# 19_RADIATOR.net
KiCad netlist of a schematic drawn in Altium Designer
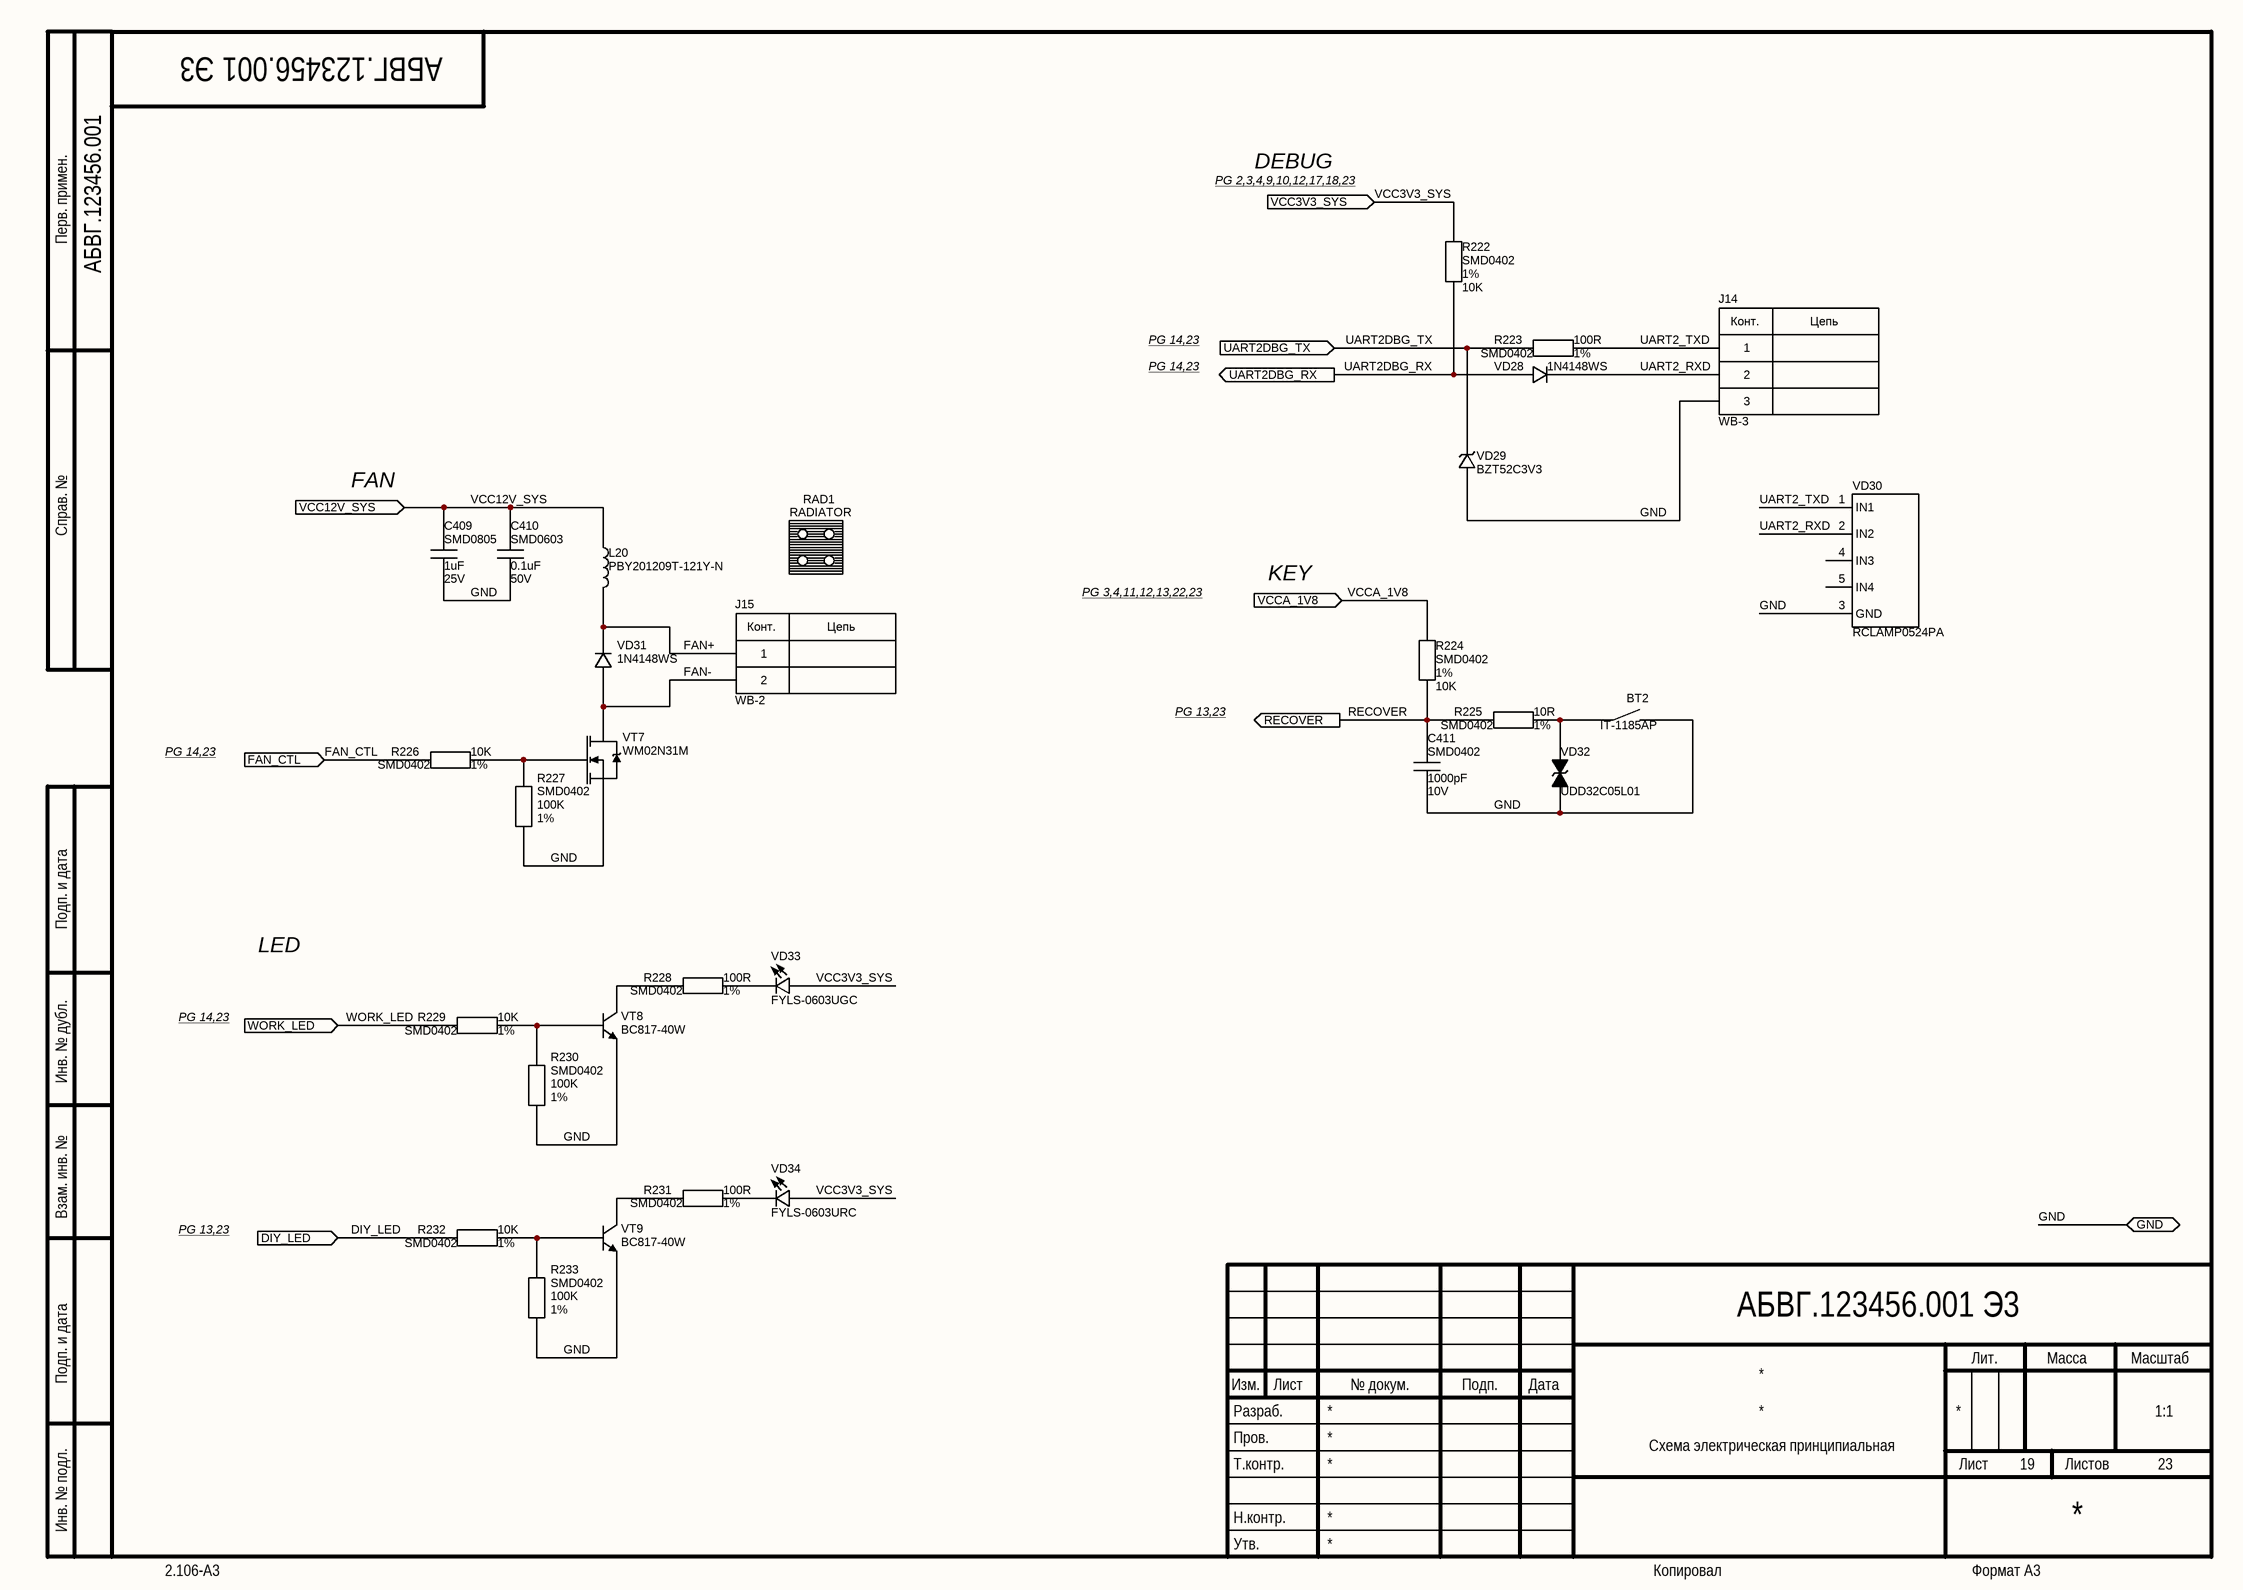
[diagram p0: 19 RADIATOR.SchDoc]

(export (version "E")
  (design (tool "Eeschema 10.0.6"))
  (components
    (comp (ref "BT2")
      (value "IT-1185AP")
      (footprint "Didur_PcbLib_1:IT-1185AP")
      (libsource (lib "Didur_SchLib_1") (part "Button_2pin"))
    )
    (comp (ref "C409")
      (value "1uF")
      (footprint "CAP_SMD_0805")
      (fields
        (field (name "PACKAGE") "SMD0805")
        (field (name "PARTNUMBER") "CC0805KKX7R8BB105")
        (field (name "VOLTAGE") "25V")
      )
      (libsource (lib "Didur_SchLib_1") (part "Ceramic_Cap"))
    )
    (comp (ref "C410")
      (value "0.1uF")
      (footprint "CAP_SMD_0603")
      (fields
        (field (name "PACKAGE") "SMD0603")
        (field (name "PARTNUMBER") "CC0603KRX7R9BB104")
        (field (name "VOLTAGE") "50V")
      )
      (libsource (lib "Didur_SchLib_1") (part "Ceramic_Cap"))
    )
    (comp (ref "C411")
      (value "1000pF")
      (footprint "Didur_PcbLib_1:CAP_SMD_0402")
      (fields
        (field (name "PACKAGE") "SMD0402")
        (field (name "PARTNUMBER") "CC0402KRX7R9BB102")
        (field (name "VOLTAGE") "10V")
      )
      (libsource (lib "Didur_SchLib_1") (part "Ceramic_Cap"))
    )
    (comp (ref "J14")
      (value "WB-3")
      (footprint "Didur_PcbLib_1:WB-3")
      (fields (field (name "PARTNUMBER") "DS1066-03M(MW-3M)"))
      (libsource (lib "Didur_SchLib_1") (part "CON3"))
    )
    (comp (ref "J15")
      (value "WB-2")
      (footprint "Didur_PcbLib_1:WB-2")
      (fields (field (name "PARTNUMBER") "DS1066-02M(MW-2M)"))
      (libsource (lib "Didur_SchLib_1") (part "CON2"))
    )
    (comp (ref "L20")
      (value "PBY201209T-121Y-N")
      (footprint "Didur_PcbLib_1:IND_SMD_0805")
      (fields (field (name "Comment") "Value"))
      (libsource (lib "Didur_SchLib_1") (part "Inductor_smal"))
    )
    (comp (ref "R222")
      (value "10K")
      (footprint "Didur_PcbLib_1:RES_SMD_0402")
      (fields
        (field (name "PACKAGE") "SMD0402")
        (field (name "PARTNUMBER") "RC0402FR-0710KL")
        (field (name "TOLERANCE") "1%")
      )
      (libsource (lib "Didur_SchLib_1") (part "Chip_Res"))
    )
    (comp (ref "R223")
      (value "100R")
      (footprint "Didur_PcbLib_1:RES_SMD_0402")
      (fields
        (field (name "PACKAGE") "SMD0402")
        (field (name "PARTNUMBER") "RC0402FR-07100RL")
        (field (name "TOLERANCE") "1%")
      )
      (libsource (lib "") (part "Chip_Res_2"))
    )
    (comp (ref "R224")
      (value "10K")
      (footprint "Didur_PcbLib_1:RES_SMD_0402")
      (fields
        (field (name "PACKAGE") "SMD0402")
        (field (name "PARTNUMBER") "RC0402FR-0710KL")
        (field (name "TOLERANCE") "1%")
      )
      (libsource (lib "Didur_SchLib_1") (part "Chip_Res"))
    )
    (comp (ref "R225")
      (value "10R")
      (footprint "Didur_PcbLib_1:RES_SMD_0402")
      (fields
        (field (name "PACKAGE") "SMD0402")
        (field (name "PARTNUMBER") "RC0402FR-0710RL")
        (field (name "TOLERANCE") "1%")
      )
      (libsource (lib "Didur_SchLib_1") (part "Chip_Res"))
    )
    (comp (ref "R226")
      (value "10K")
      (footprint "Didur_PcbLib_1:RES_SMD_0402")
      (fields
        (field (name "PACKAGE") "SMD0402")
        (field (name "PARTNUMBER") "RC0402FR-0710KL")
        (field (name "TOLERANCE") "1%")
      )
      (libsource (lib "") (part "Chip_Res_1"))
    )
    (comp (ref "R227")
      (value "100K")
      (footprint "Didur_PcbLib_1:RES_SMD_0402")
      (fields
        (field (name "PACKAGE") "SMD0402")
        (field (name "PARTNUMBER") "RC0402FR-07100KL")
        (field (name "TOLERANCE") "1%")
      )
      (libsource (lib "") (part "Chip_Res_2"))
    )
    (comp (ref "R228")
      (value "100R")
      (footprint "Didur_PcbLib_1:RES_SMD_0402")
      (fields
        (field (name "PACKAGE") "SMD0402")
        (field (name "PARTNUMBER") "RC0402FR-07100RL")
        (field (name "TOLERANCE") "1%")
      )
      (libsource (lib "") (part "Chip_Res_2"))
    )
    (comp (ref "R229")
      (value "10K")
      (footprint "Didur_PcbLib_1:RES_SMD_0402")
      (fields
        (field (name "PACKAGE") "SMD0402")
        (field (name "PARTNUMBER") "RC0402FR-0710KL")
        (field (name "TOLERANCE") "1%")
      )
      (libsource (lib "") (part "Chip_Res_1"))
    )
    (comp (ref "R230")
      (value "100K")
      (footprint "Didur_PcbLib_1:RES_SMD_0402")
      (fields
        (field (name "PACKAGE") "SMD0402")
        (field (name "PARTNUMBER") "RC0402FR-07100KL")
        (field (name "TOLERANCE") "1%")
      )
      (libsource (lib "") (part "Chip_Res_2"))
    )
    (comp (ref "R231")
      (value "100R")
      (footprint "Didur_PcbLib_1:RES_SMD_0402")
      (fields
        (field (name "PACKAGE") "SMD0402")
        (field (name "PARTNUMBER") "RC0402FR-07100RL")
        (field (name "TOLERANCE") "1%")
      )
      (libsource (lib "") (part "Chip_Res_2"))
    )
    (comp (ref "R232")
      (value "10K")
      (footprint "Didur_PcbLib_1:RES_SMD_0402")
      (fields
        (field (name "PACKAGE") "SMD0402")
        (field (name "PARTNUMBER") "RC0402FR-0710KL")
        (field (name "TOLERANCE") "1%")
      )
      (libsource (lib "") (part "Chip_Res_1"))
    )
    (comp (ref "R233")
      (value "100K")
      (footprint "Didur_PcbLib_1:RES_SMD_0402")
      (fields
        (field (name "PACKAGE") "SMD0402")
        (field (name "PARTNUMBER") "RC0402FR-07100KL")
        (field (name "TOLERANCE") "1%")
      )
      (libsource (lib "") (part "Chip_Res_2"))
    )
    (comp (ref "RAD1")
      (value "RADIATOR")
      (footprint "Didur_PcbLib_1:RK3399_RADIATOR_2")
      (libsource (lib "Didur_SchLib_1") (part "RK3399_RADIATOR_1"))
    )
    (comp (ref "VD28")
      (value "1N4148WS")
      (footprint "SOD323")
      (fields (field (name "Comment") "Diode"))
      (libsource (lib "Didur_SchLib_1") (part "Diode"))
    )
    (comp (ref "VD29")
      (value "BZT52C3V3")
      (footprint "Didur_PcbLib_1:SOD323")
      (libsource (lib "Didur_SchLib_1") (part "ZenerDiode"))
    )
    (comp (ref "VD30")
      (value "RCLAMP0524PA")
      (footprint "Didur_PcbLib_1:RCLAMP0524PA")
      (libsource (lib "Didur_SchLib_1") (part "RCLAMP0524PA"))
    )
    (comp (ref "VD31")
      (value "1N4148WS")
      (footprint "SOD323")
      (fields (field (name "Comment") "Diode"))
      (libsource (lib "Didur_SchLib_1") (part "Diode"))
    )
    (comp (ref "VD32")
      (value "UDD32C05L01")
      (footprint "Didur_PcbLib_1:SOD323")
      (fields (field (name "Comment") "TVS_Diode"))
      (libsource (lib "Didur_SchLib_1") (part "TVS_Diode"))
    )
    (comp (ref "VD33")
      (value "FYLS-0603UGC")
      (footprint "Didur_PcbLib_1:LED_0603")
      (libsource (lib "Didur_SchLib_1") (part "LED"))
    )
    (comp (ref "VD34")
      (value "FYLS-0603URC")
      (footprint "Didur_PcbLib_1:LED_0603")
      (libsource (lib "Didur_SchLib_1") (part "LED"))
    )
    (comp (ref "VT7")
      (value "WM02N31M")
      (footprint "SOT23")
      (fields (field (name "Comment") "Value"))
      (libsource (lib "Didur_SchLib_1") (part "MOSFET_N"))
    )
    (comp (ref "VT8")
      (value "BC817-40W")
      (footprint "Didur_PcbLib_1:SC-70")
      (libsource (lib "Didur_SchLib_1") (part "NPN_BEC"))
    )
    (comp (ref "VT9")
      (value "BC817-40W")
      (footprint "Didur_PcbLib_1:SC-70")
      (libsource (lib "Didur_SchLib_1") (part "NPN_BEC"))
    )
  )
  (nets
    (net (code "1") (name "/DIY_LED") (class "Default")
      (node (ref "R232") (pin "2") (pinfunction "2_2") (pintype "passive"))
    )
    (net (code "2") (name "/FAN+") (class "Default")
      (node (ref "J15") (pin "1") (pinfunction "1_1") (pintype "passive"))
      (node (ref "L20") (pin "1") (pinfunction "1_1") (pintype "passive"))
      (node (ref "VD31") (pin "2") (pinfunction "C_2") (pintype "passive"))
    )
    (net (code "3") (name "/FAN-") (class "Default")
      (node (ref "J15") (pin "2") (pinfunction "2_2") (pintype "passive"))
      (node (ref "VD31") (pin "1") (pinfunction "A_1") (pintype "passive"))
      (node (ref "VT7") (pin "3") (pinfunction "D_3") (pintype "passive"))
    )
    (net (code "4") (name "/FAN_CTL") (class "Default")
      (node (ref "R226") (pin "2") (pinfunction "2_2") (pintype "passive"))
    )
    (net (code "5") (name "/GND") (class "Default")
      (node (ref "BT2") (pin "2") (pinfunction "2_2") (pintype "passive"))
      (node (ref "C409") (pin "1") (pinfunction "1_1") (pintype "power_in"))
      (node (ref "C410") (pin "1") (pinfunction "1_1") (pintype "power_in"))
      (node (ref "C411") (pin "1") (pinfunction "1_1") (pintype "power_in"))
      (node (ref "J14") (pin "3") (pinfunction "3_3") (pintype "power_in"))
      (node (ref "R227") (pin "1") (pinfunction "1_1") (pintype "passive"))
      (node (ref "R230") (pin "1") (pinfunction "1_1") (pintype "passive"))
      (node (ref "R233") (pin "1") (pinfunction "1_1") (pintype "passive"))
      (node (ref "VD29") (pin "1") (pinfunction "A_1") (pintype "passive"))
      (node (ref "VD30") (pin "3") (pinfunction "GND_3") (pintype "passive"))
      (node (ref "VD32") (pin "1") (pinfunction "A_1") (pintype "passive"))
      (node (ref "VT7") (pin "2") (pinfunction "S_2") (pintype "passive"))
      (node (ref "VT8") (pin "2") (pinfunction "E_2") (pintype "passive"))
      (node (ref "VT9") (pin "2") (pinfunction "E_2") (pintype "passive"))
    )
    (net (code "6") (name "/RECOVER") (class "Default")
      (node (ref "C411") (pin "2") (pinfunction "2_2") (pintype "power_in"))
      (node (ref "R224") (pin "1") (pinfunction "1_1") (pintype "passive"))
      (node (ref "R225") (pin "1") (pinfunction "1_1") (pintype "passive"))
    )
    (net (code "7") (name "/UART2DBG_RX") (class "Default")
      (node (ref "R222") (pin "1") (pinfunction "1_1") (pintype "passive"))
      (node (ref "VD28") (pin "1") (pinfunction "A_1") (pintype "passive"))
    )
    (net (code "8") (name "/UART2DBG_TX") (class "Default")
      (node (ref "R223") (pin "1") (pinfunction "1_1") (pintype "passive"))
      (node (ref "VD29") (pin "2") (pinfunction "C_2") (pintype "passive"))
    )
    (net (code "9") (name "/UART2_RXD") (class "Default")
      (node (ref "J14") (pin "2") (pinfunction "2_2") (pintype "passive"))
      (node (ref "VD28") (pin "2") (pinfunction "C_2") (pintype "passive"))
      (node (ref "VD30") (pin "2") (pinfunction "IN2_2") (pintype "passive"))
    )
    (net (code "10") (name "/UART2_TXD") (class "Default")
      (node (ref "J14") (pin "1") (pinfunction "1_1") (pintype "passive"))
      (node (ref "R223") (pin "2") (pinfunction "2_2") (pintype "passive"))
      (node (ref "VD30") (pin "1") (pinfunction "IN1_1") (pintype "passive"))
    )
    (net (code "11") (name "/VCC3V3_SYS") (class "Default")
      (node (ref "R222") (pin "2") (pinfunction "2_2") (pintype "passive"))
      (node (ref "VD33") (pin "1") (pinfunction "A_1") (pintype "passive"))
      (node (ref "VD34") (pin "1") (pinfunction "A_1") (pintype "passive"))
    )
    (net (code "12") (name "/VCC12V_SYS") (class "Default")
      (node (ref "C409") (pin "2") (pinfunction "2_2") (pintype "power_in"))
      (node (ref "C410") (pin "2") (pinfunction "2_2") (pintype "power_in"))
      (node (ref "L20") (pin "2") (pinfunction "2_2") (pintype "passive"))
    )
    (net (code "13") (name "/VCCA_1V8") (class "Default")
      (node (ref "R224") (pin "2") (pinfunction "2_2") (pintype "passive"))
    )
    (net (code "14") (name "/WORK_LED") (class "Default")
      (node (ref "R229") (pin "2") (pinfunction "2_2") (pintype "passive"))
    )
    (net (code "15") (name "Net-(VD32-C)") (class "Default")
      (node (ref "BT2") (pin "1") (pinfunction "1_1") (pintype "passive"))
      (node (ref "R225") (pin "2") (pinfunction "2_2") (pintype "passive"))
      (node (ref "VD32") (pin "2") (pinfunction "C_2") (pintype "passive"))
    )
    (net (code "16") (name "Net-(VD33-C)") (class "Default")
      (node (ref "R228") (pin "2") (pinfunction "2_2") (pintype "passive"))
      (node (ref "VD33") (pin "2") (pinfunction "C_2") (pintype "passive"))
    )
    (net (code "17") (name "Net-(VD34-C)") (class "Default")
      (node (ref "R231") (pin "2") (pinfunction "2_2") (pintype "passive"))
      (node (ref "VD34") (pin "2") (pinfunction "C_2") (pintype "passive"))
    )
    (net (code "18") (name "Net-(VT7-G)") (class "Default")
      (node (ref "R226") (pin "1") (pinfunction "1_1") (pintype "passive"))
      (node (ref "R227") (pin "2") (pinfunction "2_2") (pintype "passive"))
      (node (ref "VT7") (pin "1") (pinfunction "G_1") (pintype "passive"))
    )
    (net (code "19") (name "Net-(VT8-B)") (class "Default")
      (node (ref "R229") (pin "1") (pinfunction "1_1") (pintype "passive"))
      (node (ref "R230") (pin "2") (pinfunction "2_2") (pintype "passive"))
      (node (ref "VT8") (pin "1") (pinfunction "B_1") (pintype "passive"))
    )
    (net (code "20") (name "Net-(VT8-C)") (class "Default")
      (node (ref "R228") (pin "1") (pinfunction "1_1") (pintype "passive"))
      (node (ref "VT8") (pin "3") (pinfunction "C_3") (pintype "passive"))
    )
    (net (code "21") (name "Net-(VT9-B)") (class "Default")
      (node (ref "R232") (pin "1") (pinfunction "1_1") (pintype "passive"))
      (node (ref "R233") (pin "2") (pinfunction "2_2") (pintype "passive"))
      (node (ref "VT9") (pin "1") (pinfunction "B_1") (pintype "passive"))
    )
    (net (code "22") (name "Net-(VT9-C)") (class "Default")
      (node (ref "R231") (pin "1") (pinfunction "1_1") (pintype "passive"))
      (node (ref "VT9") (pin "3") (pinfunction "C_3") (pintype "passive"))
    )
    (net (code "23") (name "unconnected-(RAD1-Pad1)") (class "Default")
      (node (ref "RAD1") (pin "1") (pinfunction "1_1") (pintype "passive"))
    )
    (net (code "24") (name "unconnected-(RAD1-Pad2)") (class "Default")
      (node (ref "RAD1") (pin "2") (pinfunction "2_2") (pintype "passive"))
    )
    (net (code "25") (name "unconnected-(RAD1-Pad3)") (class "Default")
      (node (ref "RAD1") (pin "3") (pinfunction "3_3") (pintype "passive"))
    )
    (net (code "26") (name "unconnected-(RAD1-Pad4)") (class "Default")
      (node (ref "RAD1") (pin "4") (pinfunction "4_4") (pintype "passive"))
    )
    (net (code "27") (name "unconnected-(VD30-IN3-Pad4)") (class "Default")
      (node (ref "VD30") (pin "4") (pinfunction "IN3_4") (pintype "passive"))
    )
    (net (code "28") (name "unconnected-(VD30-IN4-Pad5)") (class "Default")
      (node (ref "VD30") (pin "5") (pinfunction "IN4_5") (pintype "passive"))
    )
  )
)
